# V0p2_Main_PCB2.net
KiCad netlist of a schematic drawn in EAGLE
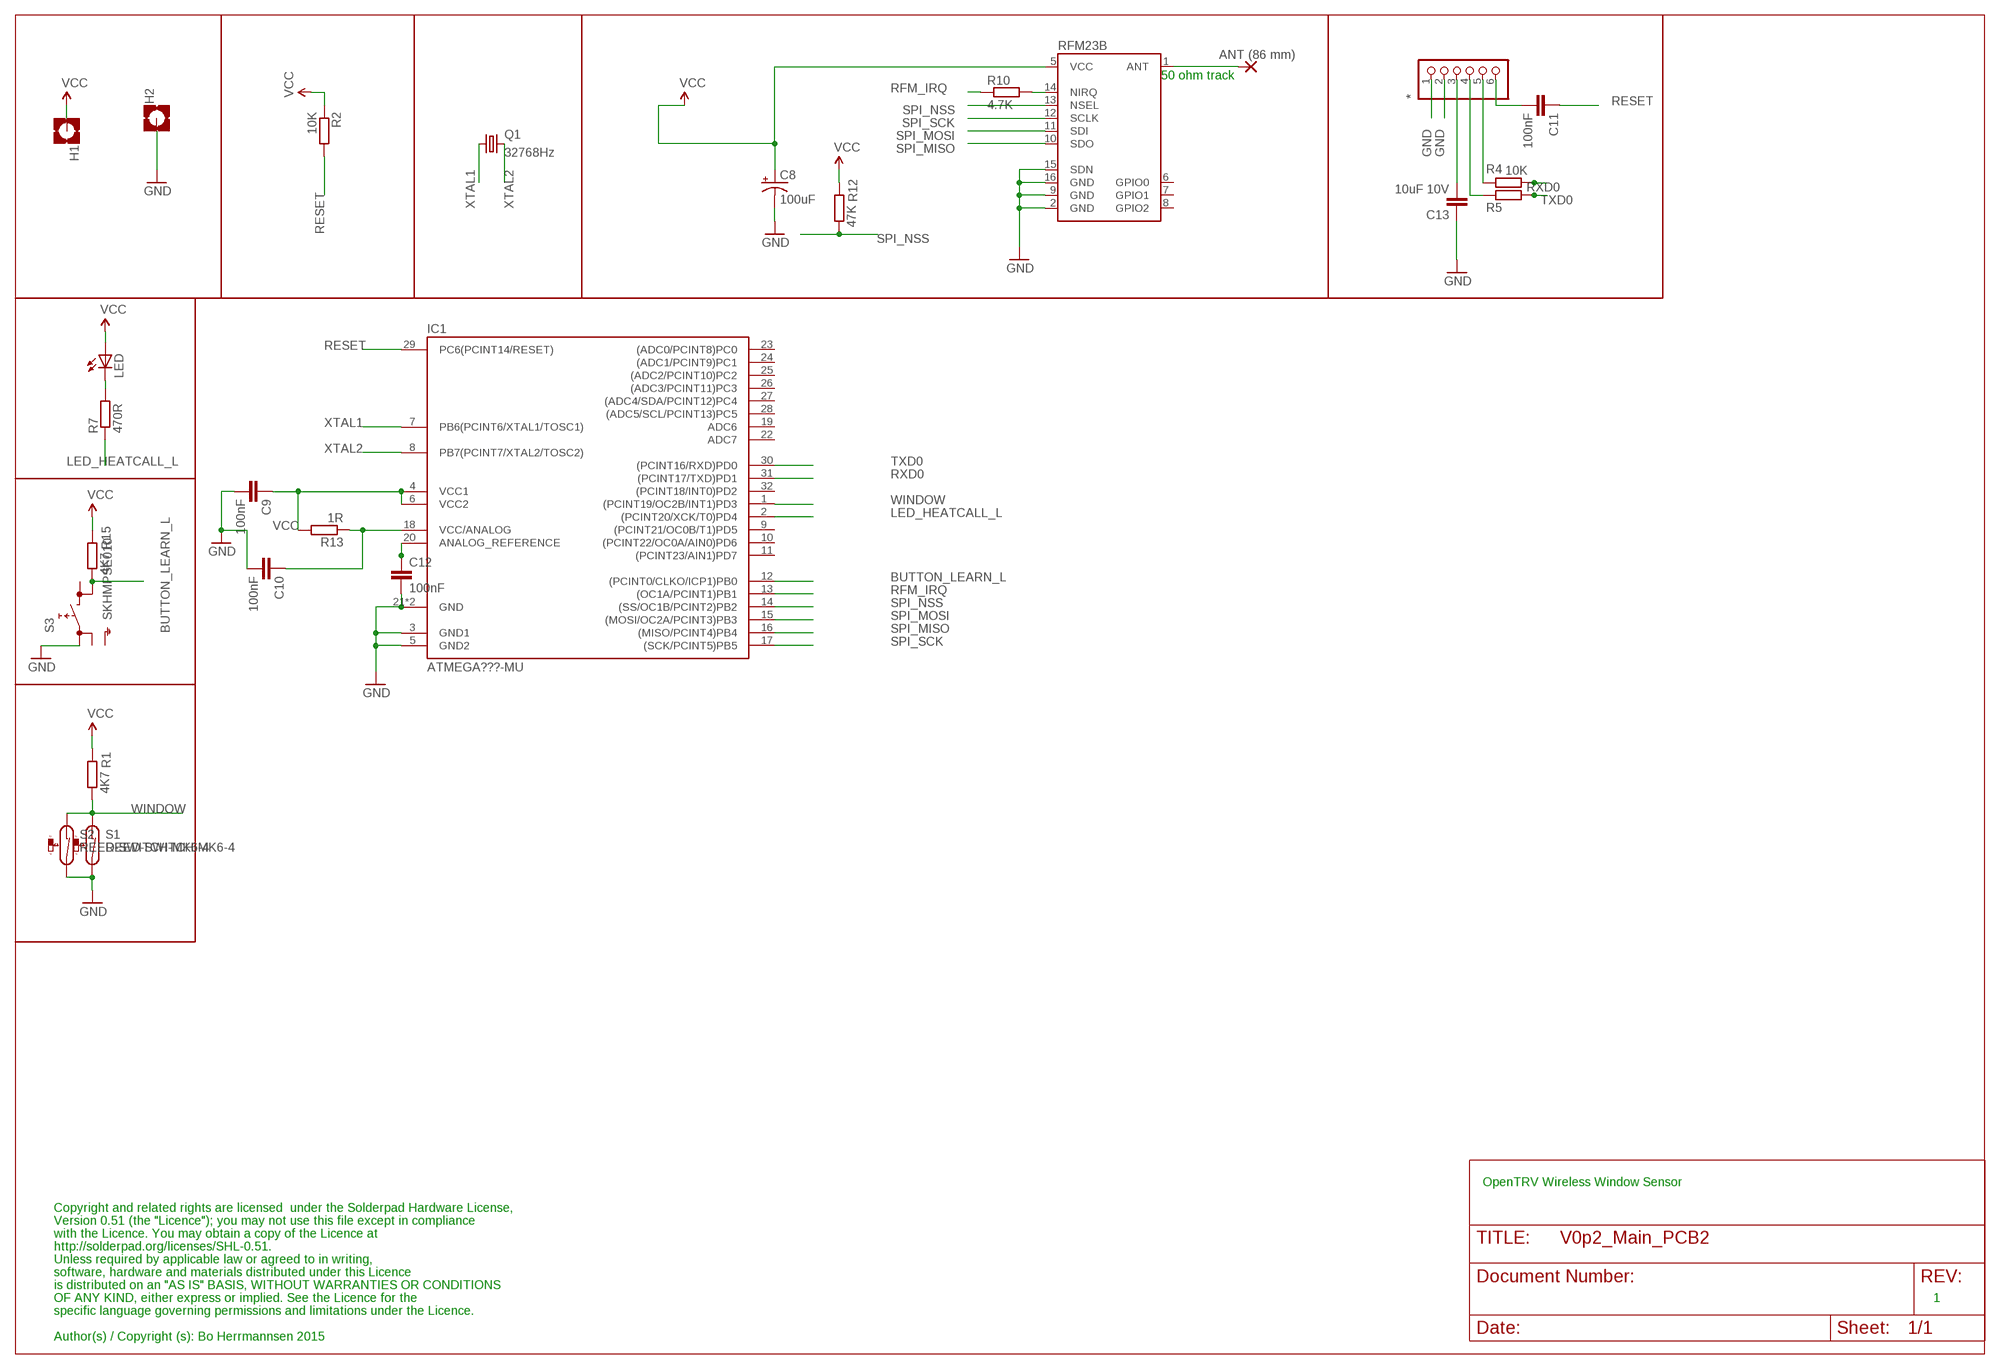
[diagram p0: schematic, sheet 1]

(export (version "E")
  (design (tool "Eeschema 10.0.6"))
  (components
    (comp (ref "*")
      (value "PINHD-1X6")
      (footprint "eagle-import:1X06")
      (libsource (lib "eagle-import") (part "PINHD-1X6"))
    )
    (comp (ref "ANT1")
      (value "ANT (86 mm)")
      (footprint "eagle-import:2,15_1,0")
      (libsource (lib "eagle-import") (part "2,15/1,0"))
    )
    (comp (ref "C8")
      (value "100uF")
      (footprint "eagle-import:EIA3216")
      (libsource (lib "eagle-import") (part "CAP_POL1206"))
    )
    (comp (ref "C9")
      (value "100nF")
      (footprint "eagle-import:C0402")
      (libsource (lib "eagle-import") (part "C-EUC0402"))
    )
    (comp (ref "C10")
      (value "100nF")
      (footprint "eagle-import:C0402")
      (libsource (lib "eagle-import") (part "C-EUC0402"))
    )
    (comp (ref "C11")
      (value "100nF")
      (footprint "eagle-import:C0402")
      (libsource (lib "eagle-import") (part "C-EUC0402"))
    )
    (comp (ref "C12")
      (value "100nF")
      (footprint "eagle-import:C0402")
      (libsource (lib "eagle-import") (part "C-EUC0402"))
    )
    (comp (ref "C13")
      (value "10uF 10V")
      (footprint "eagle-import:C0402")
      (libsource (lib "eagle-import") (part "C-EUC0402"))
    )
    (comp (ref "H1")
      (value "MOUNT-PAD-SQUARE2.8")
      (footprint "eagle-import:2,8-PAD-SQUARE")
      (libsource (lib "eagle-import") (part "MOUNT-PAD-SQUARE2.8"))
    )
    (comp (ref "H2")
      (value "MOUNT-PAD-SQUARE2.8")
      (footprint "eagle-import:2,8-PAD-SQUARE")
      (libsource (lib "eagle-import") (part "MOUNT-PAD-SQUARE2.8"))
    )
    (comp (ref "IC1")
      (value "ATMEGA???-MU")
      (footprint "eagle-import:MLF32")
      (libsource (lib "eagle-import") (part "ATMEGA8-MU"))
    )
    (comp (ref "LED")
      (value "LEDCHIPLED_0603")
      (footprint "eagle-import:CHIPLED_0603")
      (libsource (lib "eagle-import") (part "LEDCHIPLED_0603"))
    )
    (comp (ref "Q1")
      (value "32768Hz")
      (footprint "eagle-import:MC-306")
      (fields (field (name "MPN") "MC-306 60.0KHZ  100PPM ,12.5PF"))
      (libsource (lib "eagle-import") (part "MC-306"))
    )
    (comp (ref "R1")
      (value "4K7")
      (footprint "eagle-import:R0402")
      (libsource (lib "eagle-import") (part "R-EU_R0402"))
    )
    (comp (ref "R2")
      (value "10K")
      (footprint "eagle-import:R0402")
      (libsource (lib "eagle-import") (part "R-EU_R0402"))
    )
    (comp (ref "R4")
      (value "10K")
      (footprint "eagle-import:R0402")
      (libsource (lib "eagle-import") (part "R-EU_R0402"))
    )
    (comp (ref "R5")
      (value "10K")
      (footprint "eagle-import:R0402")
      (libsource (lib "eagle-import") (part "R-EU_R0402"))
    )
    (comp (ref "R7")
      (value "470R")
      (footprint "eagle-import:R0402")
      (libsource (lib "eagle-import") (part "R-EU_R0402"))
    )
    (comp (ref "R10")
      (value "4.7K")
      (footprint "eagle-import:R0402")
      (libsource (lib "eagle-import") (part "R-EU_R0402"))
    )
    (comp (ref "R12")
      (value "47K")
      (footprint "eagle-import:R0402")
      (libsource (lib "eagle-import") (part "R-EU_R0402"))
    )
    (comp (ref "R13")
      (value "1R")
      (footprint "eagle-import:R0402")
      (libsource (lib "eagle-import") (part "R-EU_R0402"))
    )
    (comp (ref "R15")
      (value "4K7")
      (footprint "eagle-import:R0402")
      (libsource (lib "eagle-import") (part "R-EU_R0402"))
    )
    (comp (ref "RFM23B")
      (value "RFM23B")
      (footprint "eagle-import:RFM23-XXX-S1")
      (libsource (lib "eagle-import") (part "RFM23B"))
    )
    (comp (ref "S1")
      (value "REED-SWITCH-MK6-4")
      (footprint "eagle-import:MK6-4")
      (libsource (lib "eagle-import") (part "REED-SWITCH-MK6-4"))
    )
    (comp (ref "S2")
      (value "REED-SWITCH-MK6-4")
      (footprint "eagle-import:MK6-4")
      (libsource (lib "eagle-import") (part "REED-SWITCH-MK6-4"))
    )
    (comp (ref "S3")
      (value "SKHMPSE010")
      (footprint "eagle-import:SKHMPXE010")
      (libsource (lib "eagle-import") (part "SKHMPE010S"))
    )
  )
  (nets
    (net (code "1") (name "/BUTTON_LEARN_L") (class "Default")
      (node (ref "IC1") (pin "12") (pinfunction "(PCINT0/CLKO/ICP1)PB0_12") (pintype "bidirectional"))
      (node (ref "R15") (pin "1") (pinfunction "1_1") (pintype "passive"))
      (node (ref "S3") (pin "4") (pinfunction "2.2_4") (pintype "passive"))
    )
    (net (code "2") (name "/LED_HEATCALL_L") (class "Default")
      (node (ref "IC1") (pin "2") (pinfunction "(PCINT20/XCK/T0)PD4_2") (pintype "bidirectional"))
      (node (ref "R7") (pin "1") (pinfunction "1_1") (pintype "passive"))
    )
    (net (code "3") (name "/RESET") (class "Default")
      (node (ref "C11") (pin "1") (pinfunction "1_1") (pintype "passive"))
      (node (ref "IC1") (pin "29") (pinfunction "PC6(PCINT14/RESET)_29") (pintype "bidirectional"))
      (node (ref "R2") (pin "2") (pinfunction "2_2") (pintype "passive"))
    )
    (net (code "4") (name "/RFM_IRQ") (class "Default")
      (node (ref "IC1") (pin "13") (pinfunction "(OC1A/PCINT1)PB1_13") (pintype "bidirectional"))
      (node (ref "R10") (pin "1") (pinfunction "1_1") (pintype "passive"))
    )
    (net (code "5") (name "/RXD0") (class "Default")
      (node (ref "IC1") (pin "31") (pinfunction "(PCINT17/TXD)PD1_31") (pintype "bidirectional"))
      (node (ref "R4") (pin "1") (pinfunction "1_1") (pintype "passive"))
    )
    (net (code "6") (name "/SPI_MISO") (class "Default")
      (node (ref "IC1") (pin "16") (pinfunction "(MISO/PCINT4)PB4_16") (pintype "bidirectional"))
      (node (ref "RFM23B") (pin "10") (pinfunction "SDO_10") (pintype "output"))
    )
    (net (code "7") (name "/SPI_MOSI") (class "Default")
      (node (ref "IC1") (pin "15") (pinfunction "(MOSI/OC2A/PCINT3)PB3_15") (pintype "bidirectional"))
      (node (ref "RFM23B") (pin "11") (pinfunction "SDI_11") (pintype "input"))
    )
    (net (code "8") (name "/SPI_NSS") (class "Default")
      (node (ref "IC1") (pin "14") (pinfunction "(SS/OC1B/PCINT2)PB2_14") (pintype "bidirectional"))
      (node (ref "R12") (pin "1") (pinfunction "1_1") (pintype "passive"))
      (node (ref "RFM23B") (pin "13") (pinfunction "NSEL_13") (pintype "input"))
    )
    (net (code "9") (name "/SPI_SCK") (class "Default")
      (node (ref "IC1") (pin "17") (pinfunction "(SCK/PCINT5)PB5_17") (pintype "bidirectional"))
      (node (ref "RFM23B") (pin "12") (pinfunction "SCLK_12") (pintype "input"))
    )
    (net (code "10") (name "/TXD0") (class "Default")
      (node (ref "IC1") (pin "30") (pinfunction "(PCINT16/RXD)PD0_30") (pintype "bidirectional"))
      (node (ref "R5") (pin "1") (pinfunction "1_1") (pintype "passive"))
    )
    (net (code "11") (name "/WINDOW") (class "Default")
      (node (ref "IC1") (pin "1") (pinfunction "(PCINT19/OC2B/INT1)PD3_1") (pintype "bidirectional"))
      (node (ref "R1") (pin "1") (pinfunction "1_1") (pintype "passive"))
      (node (ref "S1") (pin "1") (pinfunction "1_1") (pintype "passive"))
      (node (ref "S2") (pin "1") (pinfunction "1_1") (pintype "passive"))
    )
    (net (code "12") (name "/XTAL1") (class "Default")
      (node (ref "IC1") (pin "7") (pinfunction "PB6(PCINT6/XTAL1/TOSC1)_7") (pintype "bidirectional"))
      (node (ref "Q1") (pin "1") (pinfunction "1_1") (pintype "passive"))
    )
    (net (code "13") (name "/XTAL2") (class "Default")
      (node (ref "IC1") (pin "8") (pinfunction "PB7(PCINT7/XTAL2/TOSC2)_8") (pintype "bidirectional"))
      (node (ref "Q1") (pin "4") (pinfunction "2_4") (pintype "passive"))
    )
    (net (code "14") (name "GND") (class "Default")
      (node (ref "*") (pin "1") (pinfunction "1_1") (pintype "passive"))
      (node (ref "*") (pin "2") (pinfunction "2_2") (pintype "passive"))
      (node (ref "C10") (pin "2") (pinfunction "2_2") (pintype "passive"))
      (node (ref "C12") (pin "2") (pinfunction "2_2") (pintype "passive"))
      (node (ref "C13") (pin "1") (pinfunction "1_1") (pintype "passive"))
      (node (ref "C8") (pin "C") (pinfunction "-_C") (pintype "passive"))
      (node (ref "C9") (pin "2") (pinfunction "2_2") (pintype "passive"))
      (node (ref "H2") (pin "B2,8") (pinfunction "MOUNT_B2,8") (pintype "passive"))
      (node (ref "IC1") (pin "21") (pinfunction "GND_21") (pintype "power_in"))
      (node (ref "IC1") (pin "3") (pinfunction "GND1_3") (pintype "power_in"))
      (node (ref "IC1") (pin "5") (pinfunction "GND2_5") (pintype "power_in"))
      (node (ref "IC1") (pin "P$1") (pinfunction "GND_P$1") (pintype "power_in"))
      (node (ref "RFM23B") (pin "15") (pinfunction "SDN_15") (pintype "input"))
      (node (ref "RFM23B") (pin "16") (pinfunction "GND_16") (pintype "power_in"))
      (node (ref "RFM23B") (pin "2") (pinfunction "GND_2") (pintype "power_in"))
      (node (ref "RFM23B") (pin "9") (pinfunction "GND_9") (pintype "power_in"))
      (node (ref "S1") (pin "2") (pinfunction "2_2") (pintype "passive"))
      (node (ref "S2") (pin "2") (pinfunction "2_2") (pintype "passive"))
      (node (ref "S3") (pin "1") (pinfunction "1.1_1") (pintype "passive"))
    )
    (net (code "15") (name "Net-(*-Pad3)") (class "Default")
      (node (ref "*") (pin "3") (pinfunction "3_3") (pintype "passive"))
      (node (ref "C13") (pin "2") (pinfunction "2_2") (pintype "passive"))
    )
    (net (code "16") (name "Net-(*-Pad4)") (class "Default")
      (node (ref "*") (pin "4") (pinfunction "4_4") (pintype "passive"))
      (node (ref "R5") (pin "2") (pinfunction "2_2") (pintype "passive"))
    )
    (net (code "17") (name "Net-(*-Pad5)") (class "Default")
      (node (ref "*") (pin "5") (pinfunction "5_5") (pintype "passive"))
      (node (ref "R4") (pin "2") (pinfunction "2_2") (pintype "passive"))
    )
    (net (code "18") (name "Net-(*-Pad6)") (class "Default")
      (node (ref "*") (pin "6") (pinfunction "6_6") (pintype "passive"))
      (node (ref "C11") (pin "2") (pinfunction "2_2") (pintype "passive"))
    )
    (net (code "19") (name "Net-(ANT1-P)") (class "Default")
      (node (ref "ANT1") (pin "1") (pinfunction "P_1") (pintype "passive"))
      (node (ref "RFM23B") (pin "1") (pinfunction "ANT_1") (pintype "bidirectional"))
    )
    (net (code "20") (name "Net-(IC1-ANALOG_REFERENCE)") (class "Default")
      (node (ref "C12") (pin "1") (pinfunction "1_1") (pintype "passive"))
      (node (ref "IC1") (pin "20") (pinfunction "ANALOG_REFERENCE_20") (pintype "passive"))
    )
    (net (code "21") (name "Net-(IC1-VCC{slash}ANALOG)") (class "Default")
      (node (ref "C10") (pin "1") (pinfunction "1_1") (pintype "passive"))
      (node (ref "IC1") (pin "18") (pinfunction "VCC/ANALOG_18") (pintype "passive"))
      (node (ref "R13") (pin "1") (pinfunction "1_1") (pintype "passive"))
    )
    (net (code "22") (name "Net-(LED-PadC)") (class "Default")
      (node (ref "LED") (pin "C") (pinfunction "C_C") (pintype "passive"))
      (node (ref "R7") (pin "2") (pinfunction "2_2") (pintype "passive"))
    )
    (net (code "23") (name "Net-(RFM23B-NIRQ)") (class "Default")
      (node (ref "R10") (pin "2") (pinfunction "2_2") (pintype "passive"))
      (node (ref "RFM23B") (pin "14") (pinfunction "NIRQ_14") (pintype "output"))
    )
    (net (code "24") (name "VCC") (class "Default")
      (node (ref "C8") (pin "A") (pinfunction "+_A") (pintype "passive"))
      (node (ref "C9") (pin "1") (pinfunction "1_1") (pintype "passive"))
      (node (ref "H1") (pin "B2,8") (pinfunction "MOUNT_B2,8") (pintype "passive"))
      (node (ref "IC1") (pin "4") (pinfunction "VCC1_4") (pintype "power_in"))
      (node (ref "IC1") (pin "6") (pinfunction "VCC2_6") (pintype "power_in"))
      (node (ref "LED") (pin "A") (pinfunction "A_A") (pintype "passive"))
      (node (ref "R1") (pin "2") (pinfunction "2_2") (pintype "passive"))
      (node (ref "R12") (pin "2") (pinfunction "2_2") (pintype "passive"))
      (node (ref "R13") (pin "2") (pinfunction "2_2") (pintype "passive"))
      (node (ref "R15") (pin "2") (pinfunction "2_2") (pintype "passive"))
      (node (ref "R2") (pin "1") (pinfunction "1_1") (pintype "passive"))
      (node (ref "RFM23B") (pin "5") (pinfunction "VCC_5") (pintype "bidirectional"))
    )
    (net (code "25") (name "unconnected-(IC1-(ADC0{slash}PCINT8)PC0-Pad23)") (class "Default")
      (node (ref "IC1") (pin "23") (pinfunction "(ADC0/PCINT8)PC0_23") (pintype "bidirectional"))
    )
    (net (code "26") (name "unconnected-(IC1-(ADC1{slash}PCINT9)PC1-Pad24)") (class "Default")
      (node (ref "IC1") (pin "24") (pinfunction "(ADC1/PCINT9)PC1_24") (pintype "bidirectional"))
    )
    (net (code "27") (name "unconnected-(IC1-(ADC2{slash}PCINT10)PC2-Pad25)") (class "Default")
      (node (ref "IC1") (pin "25") (pinfunction "(ADC2/PCINT10)PC2_25") (pintype "bidirectional"))
    )
    (net (code "28") (name "unconnected-(IC1-(ADC3{slash}PCINT11)PC3-Pad26)") (class "Default")
      (node (ref "IC1") (pin "26") (pinfunction "(ADC3/PCINT11)PC3_26") (pintype "bidirectional"))
    )
    (net (code "29") (name "unconnected-(IC1-(ADC4{slash}SDA{slash}PCINT12)PC4-Pad27)") (class "Default")
      (node (ref "IC1") (pin "27") (pinfunction "(ADC4/SDA/PCINT12)PC4_27") (pintype "bidirectional"))
    )
    (net (code "30") (name "unconnected-(IC1-(ADC5{slash}SCL{slash}PCINT13)PC5-Pad28)") (class "Default")
      (node (ref "IC1") (pin "28") (pinfunction "(ADC5/SCL/PCINT13)PC5_28") (pintype "bidirectional"))
    )
    (net (code "31") (name "unconnected-(IC1-(PCINT18{slash}INT0)PD2-Pad32)") (class "Default")
      (node (ref "IC1") (pin "32") (pinfunction "(PCINT18/INT0)PD2_32") (pintype "bidirectional"))
    )
    (net (code "32") (name "unconnected-(IC1-(PCINT21{slash}OC0B{slash}T1)PD5-Pad9)") (class "Default")
      (node (ref "IC1") (pin "9") (pinfunction "(PCINT21/OC0B/T1)PD5_9") (pintype "bidirectional"))
    )
    (net (code "33") (name "unconnected-(IC1-(PCINT22{slash}OC0A{slash}AIN0)PD6-Pad10)") (class "Default")
      (node (ref "IC1") (pin "10") (pinfunction "(PCINT22/OC0A/AIN0)PD6_10") (pintype "bidirectional"))
    )
    (net (code "34") (name "unconnected-(IC1-(PCINT23{slash}AIN1)PD7-Pad11)") (class "Default")
      (node (ref "IC1") (pin "11") (pinfunction "(PCINT23/AIN1)PD7_11") (pintype "bidirectional"))
    )
    (net (code "35") (name "unconnected-(IC1-ADC6-Pad19)") (class "Default")
      (node (ref "IC1") (pin "19") (pinfunction "ADC6_19") (pintype "passive"))
    )
    (net (code "36") (name "unconnected-(IC1-ADC7-Pad22)") (class "Default")
      (node (ref "IC1") (pin "22") (pinfunction "ADC7_22") (pintype "passive"))
    )
    (net (code "37") (name "unconnected-(RFM23B-GPIO0-Pad6)") (class "Default")
      (node (ref "RFM23B") (pin "6") (pinfunction "GPIO0_6") (pintype "bidirectional"))
    )
    (net (code "38") (name "unconnected-(RFM23B-GPIO1-Pad7)") (class "Default")
      (node (ref "RFM23B") (pin "7") (pinfunction "GPIO1_7") (pintype "bidirectional"))
    )
    (net (code "39") (name "unconnected-(RFM23B-GPIO2-Pad8)") (class "Default")
      (node (ref "RFM23B") (pin "8") (pinfunction "GPIO2_8") (pintype "bidirectional"))
    )
    (net (code "40") (name "unconnected-(S3-1.2-Pad2)") (class "Default")
      (node (ref "S3") (pin "2") (pinfunction "1.2_2") (pintype "passive"))
    )
    (net (code "41") (name "unconnected-(S3-2.1-Pad3)") (class "Default")
      (node (ref "S3") (pin "3") (pinfunction "2.1_3") (pintype "passive"))
    )
    (net (code "42") (name "unconnected-(S3-SH-Pad5)") (class "Default")
      (node (ref "S3") (pin "5") (pinfunction "SH_5") (pintype "passive"))
    )
  )
)
